# lightswitchx2.net
KiCad netlist of a schematic drawn in EAGLE
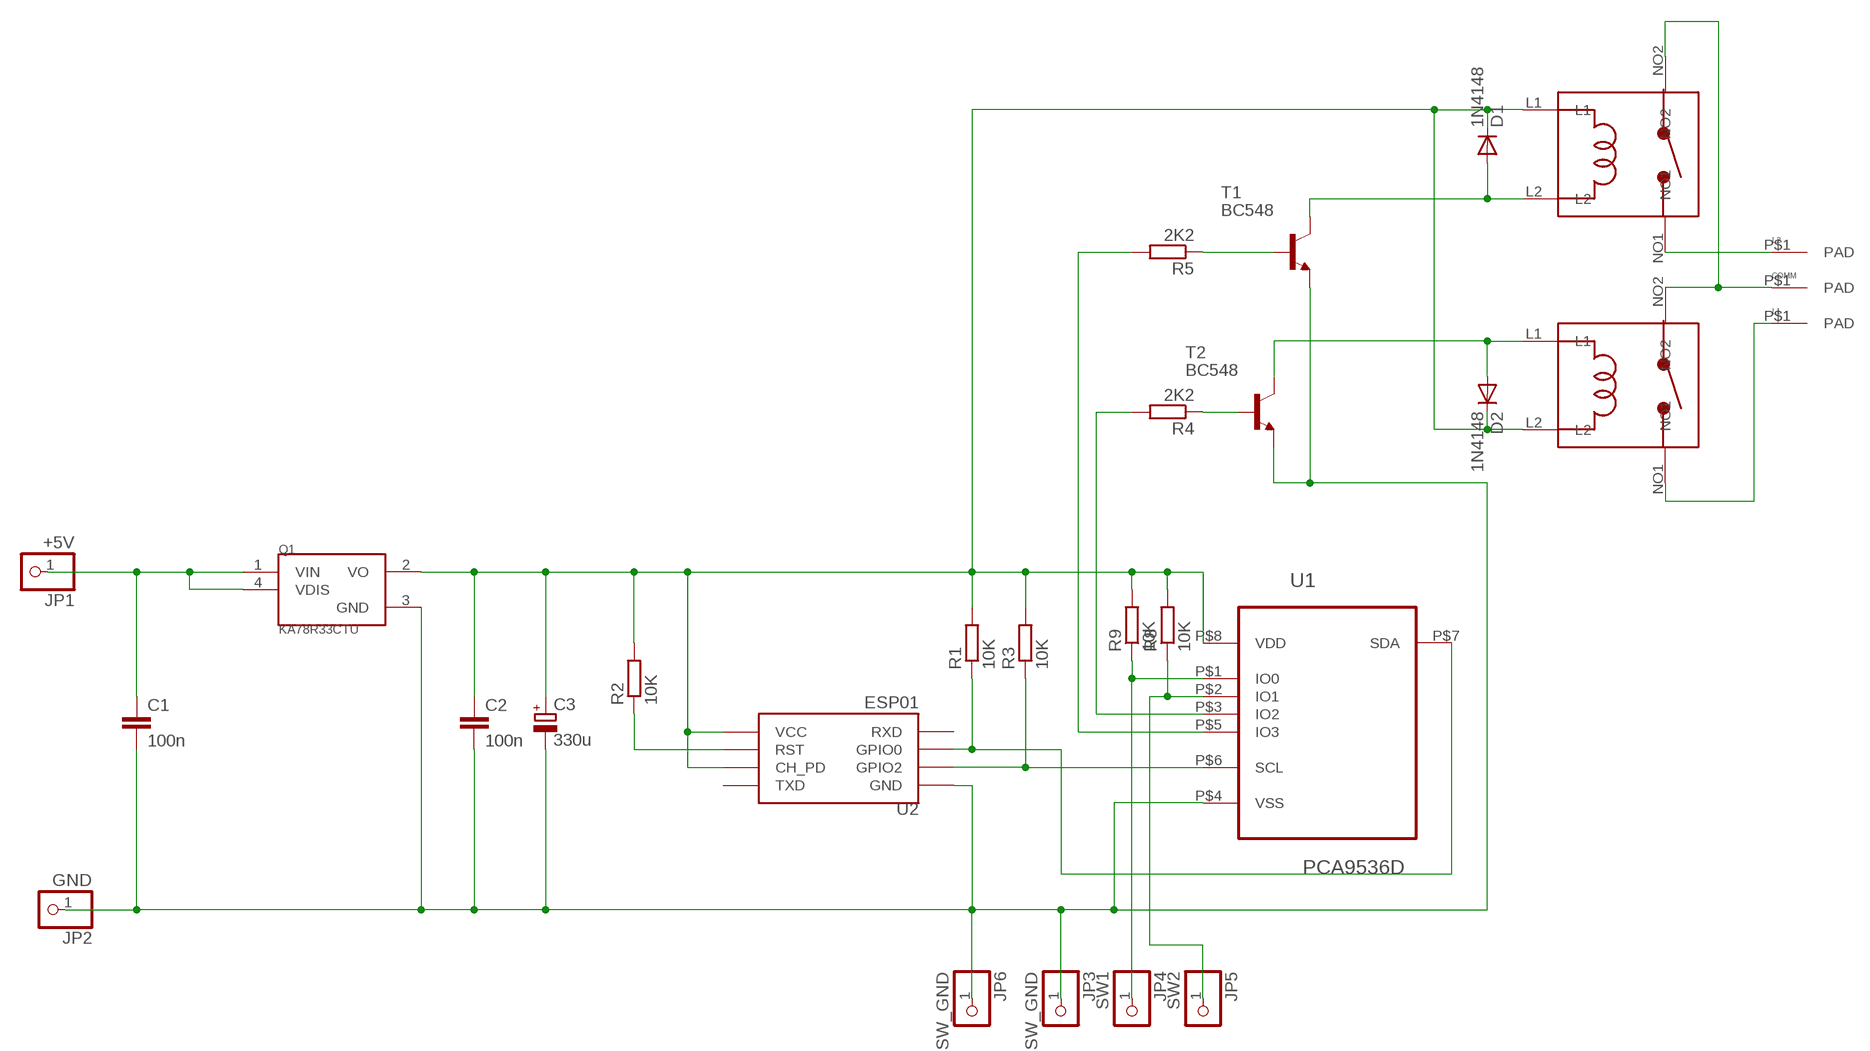
[diagram p0: schematic, sheet 1]

(export (version "E")
  (design (tool "Eeschema 10.0.6"))
  (components
    (comp (ref "C1")
      (value "100n")
      (footprint "eagle-import:C050-024X044")
      (libsource (lib "eagle-import") (part "C-EU050-024X044"))
    )
    (comp (ref "C2")
      (value "100n")
      (footprint "eagle-import:C050-024X044")
      (libsource (lib "eagle-import") (part "C-EU050-024X044"))
    )
    (comp (ref "C3")
      (value "330u")
      (footprint "eagle-import:E2-5")
      (libsource (lib "eagle-import") (part "CPOL-EUE2-5"))
    )
    (comp (ref "COMM")
      (value "PAD")
      (footprint "eagle-import:PAD")
      (libsource (lib "eagle-import") (part "PAD"))
    )
    (comp (ref "D1")
      (value "1N4148")
      (footprint "eagle-import:DO35-7")
      (libsource (lib "eagle-import") (part "1N4148DO35-7"))
    )
    (comp (ref "D2")
      (value "1N4148")
      (footprint "eagle-import:DO35-7")
      (libsource (lib "eagle-import") (part "1N4148DO35-7"))
    )
    (comp (ref "JP1")
      (value "+5V")
      (footprint "eagle-import:1X01")
      (libsource (lib "eagle-import") (part "PINHD-1X1"))
    )
    (comp (ref "JP2")
      (value "GND")
      (footprint "eagle-import:1X01")
      (libsource (lib "eagle-import") (part "PINHD-1X1"))
    )
    (comp (ref "JP3")
      (value "SW_GND")
      (footprint "eagle-import:1X01-CLEANBIG")
      (libsource (lib "eagle-import") (part "PINHD-1X1CB"))
    )
    (comp (ref "JP4")
      (value "SW1")
      (footprint "eagle-import:1X01-CLEANBIG")
      (libsource (lib "eagle-import") (part "PINHD-1X1CB"))
    )
    (comp (ref "JP5")
      (value "SW2")
      (footprint "eagle-import:1X01-CLEANBIG")
      (libsource (lib "eagle-import") (part "PINHD-1X1CB"))
    )
    (comp (ref "JP6")
      (value "SW_GND")
      (footprint "eagle-import:1X01-CLEANBIG")
      (libsource (lib "eagle-import") (part "PINHD-1X1CB"))
    )
    (comp (ref "L1")
      (value "L1")
      (footprint "eagle-import:PAD")
      (libsource (lib "eagle-import") (part "PAD"))
    )
    (comp (ref "L2") (value "X") (footprint "eagle-import:PAD") (libsource (lib "eagle-import") (part "PAD")))
    (comp (ref "Q1")
      (value "KA78R33CTU")
      (footprint "eagle-import:TO-220-4")
      (fields (field (name "MF") "Fairchild Semiconductor"))
      (libsource (lib "eagle-import") (part "KA78R33CTU"))
    )
    (comp (ref "R1")
      (value "10K")
      (footprint "eagle-import:0207_10")
      (libsource (lib "eagle-import") (part "R-EU_0207/10"))
    )
    (comp (ref "R2")
      (value "10K")
      (footprint "eagle-import:0204_7")
      (libsource (lib "eagle-import") (part "R-EU_0204/7"))
    )
    (comp (ref "R3")
      (value "10K")
      (footprint "eagle-import:0204_7")
      (libsource (lib "eagle-import") (part "R-EU_0204/7"))
    )
    (comp (ref "R4")
      (value "2K2")
      (footprint "eagle-import:0204_7")
      (libsource (lib "eagle-import") (part "R-EU_0204/7"))
    )
    (comp (ref "R5")
      (value "2K2")
      (footprint "eagle-import:0204_7")
      (libsource (lib "eagle-import") (part "R-EU_0204/7"))
    )
    (comp (ref "R8")
      (value "10K")
      (footprint "eagle-import:0207_7")
      (libsource (lib "eagle-import") (part "R-EU_0207/7"))
    )
    (comp (ref "R9")
      (value "10K")
      (footprint "eagle-import:0207_10")
      (libsource (lib "eagle-import") (part "R-EU_0207/10"))
    )
    (comp (ref "REL1")
      (value "LEG1A-5")
      (footprint "eagle-import:LEG-1A-5")
      (libsource (lib "eagle-import") (part "LEG1A-5"))
    )
    (comp (ref "REL2")
      (value "LEG1A-5")
      (footprint "eagle-import:LEG-1A-5")
      (libsource (lib "eagle-import") (part "LEG1A-5"))
    )
    (comp (ref "T1")
      (value "BC548")
      (footprint "eagle-import:TO92-EBC")
      (libsource (lib "eagle-import") (part "BC548"))
    )
    (comp (ref "T2")
      (value "BC548")
      (footprint "eagle-import:TO92-EBC")
      (libsource (lib "eagle-import") (part "BC548"))
    )
    (comp (ref "U1")
      (value "PCA9536D")
      (footprint "eagle-import:ADAPTER")
      (libsource (lib "eagle-import") (part "PCA9536D,118ADAPTER"))
    )
    (comp (ref "U2")
      (value "ESP01")
      (footprint "eagle-import:ESP01")
      (libsource (lib "eagle-import") (part "ESP01"))
    )
  )
  (nets
    (net (code "1") (name "Net-(COMM-PAD)") (class "Default")
      (node (ref "COMM") (pin "P$1") (pinfunction "PAD_P$1") (pintype "bidirectional"))
      (node (ref "REL1") (pin "NO2") (pinfunction "NO2_NO2") (pintype "bidirectional"))
      (node (ref "REL2") (pin "NO2") (pinfunction "NO2_NO2") (pintype "bidirectional"))
    )
    (net (code "2") (name "Net-(D1-PadA)") (class "Default")
      (node (ref "D1") (pin "A") (pinfunction "A_A") (pintype "passive"))
      (node (ref "REL2") (pin "L2") (pinfunction "L2_L2") (pintype "bidirectional"))
      (node (ref "T1") (pin "C") (pinfunction "C_C") (pintype "passive"))
    )
    (net (code "3") (name "Net-(D2-PadA)") (class "Default")
      (node (ref "D2") (pin "A") (pinfunction "A_A") (pintype "passive"))
      (node (ref "REL1") (pin "L1") (pinfunction "L1_L1") (pintype "bidirectional"))
      (node (ref "T2") (pin "C") (pinfunction "C_C") (pintype "passive"))
    )
    (net (code "4") (name "Net-(L1-PAD)") (class "Default")
      (node (ref "L1") (pin "P$1") (pinfunction "PAD_P$1") (pintype "bidirectional"))
      (node (ref "REL1") (pin "NO1") (pinfunction "NO1_NO1") (pintype "bidirectional"))
    )
    (net (code "5") (name "Net-(L2-PAD)") (class "Default")
      (node (ref "L2") (pin "P$1") (pinfunction "PAD_P$1") (pintype "bidirectional"))
      (node (ref "REL2") (pin "NO1") (pinfunction "NO1_NO1") (pintype "bidirectional"))
    )
    (net (code "6") (name "Net-(Q1-GND)") (class "Default")
      (node (ref "C1") (pin "2") (pinfunction "2_2") (pintype "passive"))
      (node (ref "C2") (pin "2") (pinfunction "2_2") (pintype "passive"))
      (node (ref "C3") (pin "-") (pinfunction "-_-") (pintype "passive"))
      (node (ref "JP2") (pin "1") (pinfunction "1_1") (pintype "passive"))
      (node (ref "JP3") (pin "1") (pinfunction "1_1") (pintype "passive"))
      (node (ref "JP6") (pin "1") (pinfunction "1_1") (pintype "passive"))
      (node (ref "Q1") (pin "3") (pinfunction "GND_3") (pintype "passive"))
      (node (ref "T1") (pin "E") (pinfunction "E_E") (pintype "passive"))
      (node (ref "T2") (pin "E") (pinfunction "E_E") (pintype "passive"))
      (node (ref "U1") (pin "P$4") (pinfunction "VSS_P$4") (pintype "power_in"))
      (node (ref "U2") (pin "GND") (pinfunction "GND_GND") (pintype "bidirectional"))
    )
    (net (code "7") (name "Net-(Q1-VDIS)") (class "Default")
      (node (ref "C1") (pin "1") (pinfunction "1_1") (pintype "passive"))
      (node (ref "JP1") (pin "1") (pinfunction "1_1") (pintype "passive"))
      (node (ref "Q1") (pin "1") (pinfunction "VIN_1") (pintype "input"))
      (node (ref "Q1") (pin "4") (pinfunction "VDIS_4") (pintype "passive"))
    )
    (net (code "8") (name "Net-(Q1-VO)") (class "Default")
      (node (ref "C2") (pin "1") (pinfunction "1_1") (pintype "passive"))
      (node (ref "C3") (pin "+") (pinfunction "+_+") (pintype "passive"))
      (node (ref "D1") (pin "C") (pinfunction "C_C") (pintype "passive"))
      (node (ref "D2") (pin "C") (pinfunction "C_C") (pintype "passive"))
      (node (ref "Q1") (pin "2") (pinfunction "VO_2") (pintype "output"))
      (node (ref "R1") (pin "2") (pinfunction "2_2") (pintype "passive"))
      (node (ref "R2") (pin "2") (pinfunction "2_2") (pintype "passive"))
      (node (ref "R3") (pin "2") (pinfunction "2_2") (pintype "passive"))
      (node (ref "R8") (pin "2") (pinfunction "2_2") (pintype "passive"))
      (node (ref "R9") (pin "2") (pinfunction "2_2") (pintype "passive"))
      (node (ref "REL1") (pin "L2") (pinfunction "L2_L2") (pintype "bidirectional"))
      (node (ref "REL2") (pin "L1") (pinfunction "L1_L1") (pintype "bidirectional"))
      (node (ref "U1") (pin "P$8") (pinfunction "VDD_P$8") (pintype "power_in"))
      (node (ref "U2") (pin "CH_PD") (pinfunction "CH_PD_CH_PD") (pintype "bidirectional"))
      (node (ref "U2") (pin "VCC") (pinfunction "VCC_VCC") (pintype "bidirectional"))
    )
    (net (code "9") (name "Net-(R2-Pad1)") (class "Default")
      (node (ref "R2") (pin "1") (pinfunction "1_1") (pintype "passive"))
      (node (ref "U2") (pin "RST") (pinfunction "RST_RST") (pintype "bidirectional"))
    )
    (net (code "10") (name "Net-(R4-Pad1)") (class "Default")
      (node (ref "R4") (pin "1") (pinfunction "1_1") (pintype "passive"))
      (node (ref "T2") (pin "B") (pinfunction "B_B") (pintype "passive"))
    )
    (net (code "11") (name "Net-(R5-Pad1)") (class "Default")
      (node (ref "R5") (pin "1") (pinfunction "1_1") (pintype "passive"))
      (node (ref "T1") (pin "B") (pinfunction "B_B") (pintype "passive"))
    )
    (net (code "12") (name "Net-(U1-IO0)") (class "Default")
      (node (ref "JP4") (pin "1") (pinfunction "1_1") (pintype "passive"))
      (node (ref "R9") (pin "1") (pinfunction "1_1") (pintype "passive"))
      (node (ref "U1") (pin "P$1") (pinfunction "IO0_P$1") (pintype "bidirectional"))
    )
    (net (code "13") (name "Net-(U1-IO1)") (class "Default")
      (node (ref "JP5") (pin "1") (pinfunction "1_1") (pintype "passive"))
      (node (ref "R8") (pin "1") (pinfunction "1_1") (pintype "passive"))
      (node (ref "U1") (pin "P$2") (pinfunction "IO1_P$2") (pintype "bidirectional"))
    )
    (net (code "14") (name "Net-(U1-IO2)") (class "Default")
      (node (ref "R4") (pin "2") (pinfunction "2_2") (pintype "passive"))
      (node (ref "U1") (pin "P$3") (pinfunction "IO2_P$3") (pintype "bidirectional"))
    )
    (net (code "15") (name "Net-(U1-IO3)") (class "Default")
      (node (ref "R5") (pin "2") (pinfunction "2_2") (pintype "passive"))
      (node (ref "U1") (pin "P$5") (pinfunction "IO3_P$5") (pintype "bidirectional"))
    )
    (net (code "16") (name "Net-(U1-SCL)") (class "Default")
      (node (ref "R3") (pin "1") (pinfunction "1_1") (pintype "passive"))
      (node (ref "U1") (pin "P$6") (pinfunction "SCL_P$6") (pintype "input"))
      (node (ref "U2") (pin "GPIO2") (pinfunction "GPIO2_GPIO2") (pintype "bidirectional"))
    )
    (net (code "17") (name "Net-(U1-SDA)") (class "Default")
      (node (ref "R1") (pin "1") (pinfunction "1_1") (pintype "passive"))
      (node (ref "U1") (pin "P$7") (pinfunction "SDA_P$7") (pintype "bidirectional"))
      (node (ref "U2") (pin "GPIO0") (pinfunction "GPIO0_GPIO0") (pintype "bidirectional"))
    )
    (net (code "18") (name "unconnected-(U2-RXD-PadRX)") (class "Default")
      (node (ref "U2") (pin "RX") (pinfunction "RXD_RX") (pintype "bidirectional"))
    )
    (net (code "19") (name "unconnected-(U2-TXD-PadTX)") (class "Default")
      (node (ref "U2") (pin "TX") (pinfunction "TXD_TX") (pintype "bidirectional"))
    )
  )
)
